# RS485_FD.net
KiCad netlist of a schematic drawn in Altium Designer
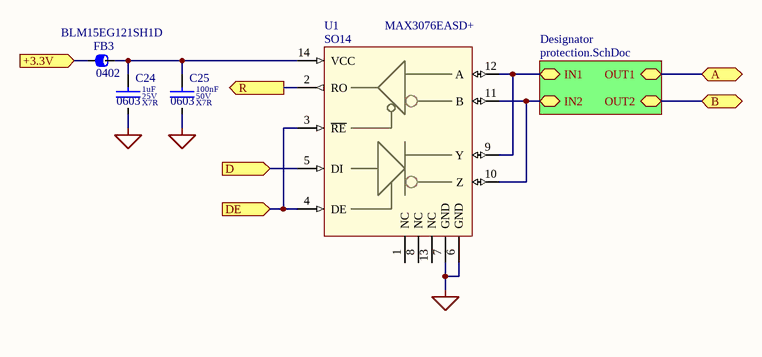
[diagram p0: RS485_FD.SchDoc]

(export (version "E")
  (design (tool "Eeschema 10.0.6"))
  (components
    (comp (ref "C24")
      (value "1uF")
      (footprint "C_0603_1608")
      (description "Capacitor")
      (fields
        (field (name "DIELECTRIC") "X7R")
        (field (name "VOLTAGE") "25V")
        (field (name "SCH_FOOTPRINT") "0603")
        (field (name "PART NUMBER") "C_1uF_25V_X7R_0603_10")
        (field (name "MANUFACTURER") "Samsung")
      )
      (libsource (lib "Library") (part "C"))
    )
    (comp (ref "C25")
      (value "100nF")
      (footprint "C_0603_1608")
      (description "Capacitor")
      (fields
        (field (name "DIELECTRIC") "X7R")
        (field (name "VOLTAGE") "50V")
        (field (name "SCH_FOOTPRINT") "0603")
        (field (name "PART NUMBER") "C_100nF_50V_X7R_0603_5")
        (field (name "MANUFACTURER") "Samsung")
      )
      (libsource (lib "Library") (part "C"))
    )
    (comp (ref "FB3")
      (value "Ferrite bead")
      (footprint "FB_0402_1005")
      (description "Ferrite Bead")
      (fields
        (field (name "PART NUMBER") "FB_BLM15EG121SH1D")
        (field (name "SCH_FOOTPRINT") "0402")
        (field (name "MANUFACTURER") "Murata")
        (field (name "MANUFACTURER PART NUMBER") "BLM15EG121SH1D")
      )
      (libsource (lib "Library") (part "FB"))
    )
    (comp (ref "U1")
      (value "MAX3076EASD+")
      (footprint "SOP14_SO14_SOIC14_4X9X18")
      (description "RS-485/RS-422 Transceivers, +3.3V,  ±15kV ESD-Protected, Fail-Safe, Hot-Swap")
      (fields
        (field (name "SCH_FOOTPRINT") "SO14")
        (field (name "PART NUMBER") "U_MAX3076EASD+")
        (field (name "MANUFACTURER") "Maxim Integrated")
      )
      (libsource (lib "Library") (part "U_MAX3076E"))
    )
  )
  (nets
    (net (code "1") (name "/+3.3V") (class "Default") (node (ref "FB3") (pin "1") (pintype "input")))
    (net (code "4") (name "/D") (class "Default")
      (node (ref "U1") (pin "5") (pinfunction "DI_5") (pintype "input"))
    )
    (net (code "5") (name "/DE") (class "Default")
      (node (ref "U1") (pin "3") (pinfunction "~{RE}_3") (pintype "input"))
      (node (ref "U1") (pin "4") (pinfunction "DE_4") (pintype "input"))
    )
    (net (code "6") (name "/IN1") (class "Default")
      (node (ref "U1") (pin "12") (pinfunction "A_12") (pintype "bidirectional"))
      (node (ref "U1") (pin "9") (pinfunction "Y_9") (pintype "bidirectional"))
    )
    (net (code "7") (name "/IN2") (class "Default")
      (node (ref "U1") (pin "10") (pinfunction "Z_10") (pintype "bidirectional"))
      (node (ref "U1") (pin "11") (pinfunction "B_11") (pintype "bidirectional"))
    )
    (net (code "8") (name "/R") (class "Default")
      (node (ref "U1") (pin "2") (pinfunction "RO_2") (pintype "output"))
    )
    (net (code "9") (name "GND") (class "Default")
      (node (ref "C24") (pin "2") (pinfunction "2_2") (pintype "passive"))
      (node (ref "C25") (pin "2") (pinfunction "2_2") (pintype "passive"))
      (node (ref "U1") (pin "6") (pinfunction "GND_6") (pintype "power_in"))
      (node (ref "U1") (pin "7") (pinfunction "GND_7") (pintype "power_in"))
    )
    (net (code "10") (name "Net-(U1-VCC)") (class "Default")
      (node (ref "C24") (pin "1") (pinfunction "1_1") (pintype "passive"))
      (node (ref "C25") (pin "1") (pinfunction "1_1") (pintype "passive"))
      (node (ref "FB3") (pin "2") (pintype "output"))
      (node (ref "U1") (pin "14") (pinfunction "VCC_14") (pintype "input"))
    )
    (net (code "11") (name "unconnected-(U1-NC-Pad1)") (class "Default")
      (node (ref "U1") (pin "1") (pinfunction "NC_1") (pintype "passive"))
    )
    (net (code "12") (name "unconnected-(U1-NC-Pad8)") (class "Default")
      (node (ref "U1") (pin "8") (pinfunction "NC_8") (pintype "passive"))
    )
    (net (code "13") (name "unconnected-(U1-NC-Pad13)") (class "Default")
      (node (ref "U1") (pin "13") (pinfunction "NC_13") (pintype "passive"))
    )
  )
)
